# UWB-Adapter_Sch.net
KiCad netlist of a schematic drawn in Altium Designer
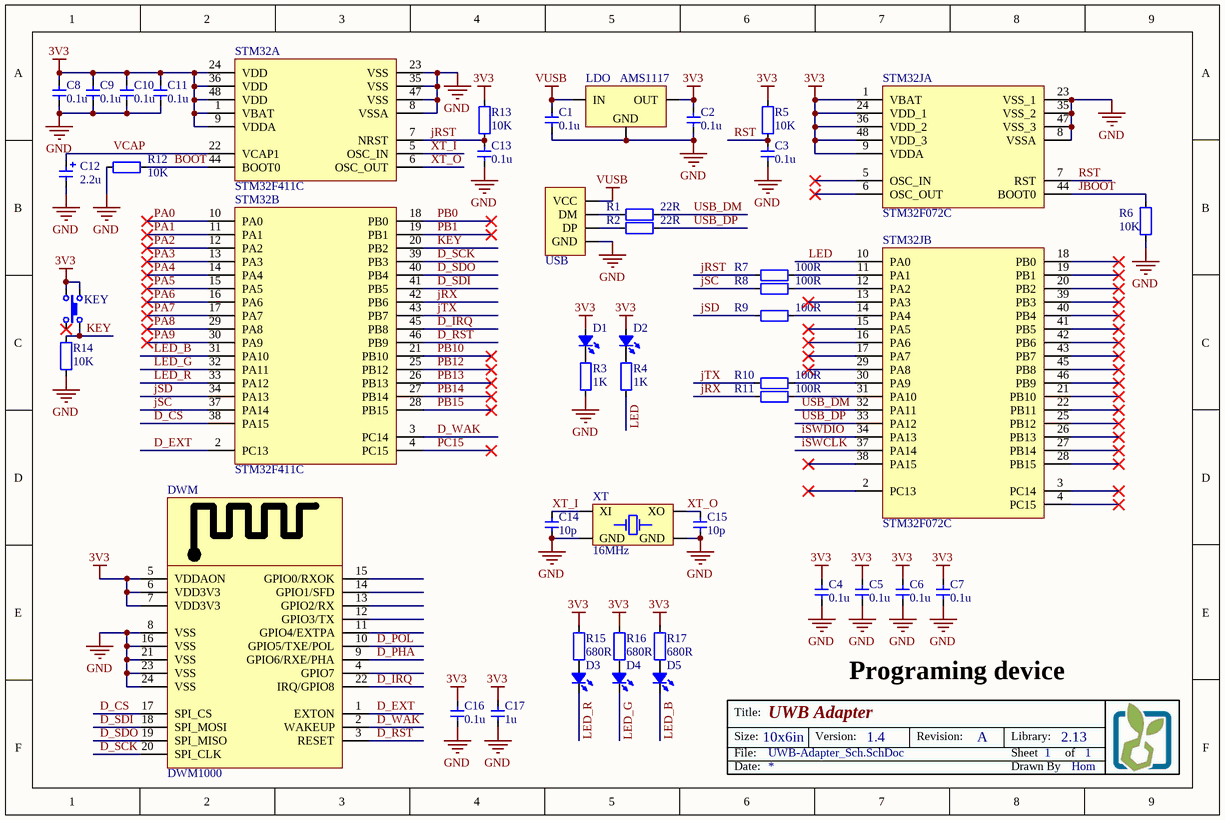
[diagram p0: UWB-Adapter_Sch.SchDoc]

(export (version "E")
  (design (tool "Eeschema 10.0.6"))
  (components
    (comp (ref "C1")
      (value "0.1u")
      (footprint "PCB_PassiveCap:CAP_0603")
      (description "Capacitor")
      (fields (field (name "Comment") "Cap_0603"))
      (libsource (lib "SCH_Passive") (part "Cap_0603"))
    )
    (comp (ref "C2")
      (value "0.1u")
      (footprint "PCB_PassiveCap:CAP_0603")
      (description "Capacitor")
      (fields (field (name "Comment") "Cap_0603"))
      (libsource (lib "SCH_Passive") (part "Cap_0603"))
    )
    (comp (ref "C3")
      (value "0.1u")
      (footprint "PCB_PassiveCap:CAP_0603")
      (description "Capacitor")
      (fields (field (name "Comment") "Cap_0603"))
      (libsource (lib "SCH_Passive") (part "Cap_0603"))
    )
    (comp (ref "C4")
      (value "0.1u")
      (footprint "PCB_PassiveCap:CAP_0603")
      (description "Capacitor")
      (fields (field (name "Comment") "Cap_0603"))
      (libsource (lib "SCH_Passive") (part "Cap_0603"))
    )
    (comp (ref "C5")
      (value "0.1u")
      (footprint "PCB_PassiveCap:CAP_0603")
      (description "Capacitor")
      (fields (field (name "Comment") "Cap_0603"))
      (libsource (lib "SCH_Passive") (part "Cap_0603"))
    )
    (comp (ref "C6")
      (value "0.1u")
      (footprint "PCB_PassiveCap:CAP_0603")
      (description "Capacitor")
      (fields (field (name "Comment") "Cap_0603"))
      (libsource (lib "SCH_Passive") (part "Cap_0603"))
    )
    (comp (ref "C7")
      (value "0.1u")
      (footprint "PCB_PassiveCap:CAP_0603")
      (description "Capacitor")
      (fields (field (name "Comment") "Cap_0603"))
      (libsource (lib "SCH_Passive") (part "Cap_0603"))
    )
    (comp (ref "C8")
      (value "0.1u")
      (footprint "PCB_PassiveCap:CAP_0603")
      (description "Capacitor")
      (fields (field (name "Comment") "Cap_0603"))
      (libsource (lib "SCH_Passive") (part "Cap_0603"))
    )
    (comp (ref "C9")
      (value "0.1u")
      (footprint "PCB_PassiveCap:CAP_0603")
      (description "Capacitor")
      (fields (field (name "Comment") "Cap_0603"))
      (libsource (lib "SCH_Passive") (part "Cap_0603"))
    )
    (comp (ref "C10")
      (value "0.1u")
      (footprint "PCB_PassiveCap:CAP_0603")
      (description "Capacitor")
      (fields (field (name "Comment") "Cap_0603"))
      (libsource (lib "SCH_Passive") (part "Cap_0603"))
    )
    (comp (ref "C11")
      (value "0.1u")
      (footprint "PCB_PassiveCap:CAP_0603")
      (description "Capacitor")
      (fields (field (name "Comment") "Cap_0603"))
      (libsource (lib "SCH_Passive") (part "Cap_0603"))
    )
    (comp (ref "C12")
      (value "2.2u")
      (footprint "PCB_PassiveCap:CAP_TAN_P0805")
      (description "Capacitor")
      (fields (field (name "Comment") "Cap_Tan_0805"))
      (libsource (lib "SCH_Passive") (part "Cap_Tan_0805"))
    )
    (comp (ref "C13")
      (value "0.1u")
      (footprint "PCB_PassiveCap:CAP_0603")
      (description "Capacitor")
      (fields (field (name "Comment") "Cap_0603"))
      (libsource (lib "SCH_Passive") (part "Cap_0603"))
    )
    (comp (ref "C14")
      (value "10p")
      (footprint "PCB_PassiveCap:CAP_0603")
      (description "Capacitor")
      (fields (field (name "Comment") "Cap_0603"))
      (libsource (lib "SCH_Passive") (part "Cap_0603"))
    )
    (comp (ref "C15")
      (value "10p")
      (footprint "PCB_PassiveCap:CAP_0603")
      (description "Capacitor")
      (fields (field (name "Comment") "Cap_0603"))
      (libsource (lib "SCH_Passive") (part "Cap_0603"))
    )
    (comp (ref "C16")
      (value "0.1u")
      (footprint "PCB_PassiveCap:CAP_0603")
      (description "Capacitor")
      (fields (field (name "Comment") "Cap_0603"))
      (libsource (lib "SCH_Passive") (part "Cap_0603"))
    )
    (comp (ref "C17")
      (value "1u")
      (footprint "PCB_PassiveCap:CAP_0603")
      (description "Capacitor")
      (fields (field (name "Comment") "Cap_0603"))
      (libsource (lib "SCH_Passive") (part "Cap_0603"))
    )
    (comp (ref "D1")
      (value "LED_0603")
      (footprint "PCB_ActiveLED:LED_0603_YELLOW")
      (description "LED")
      (libsource (lib "SCH_Active") (part "LED_0603"))
    )
    (comp (ref "D2")
      (value "LED_0603")
      (footprint "PCB_ActiveLED:LED_0603_ORANGE")
      (description "LED")
      (libsource (lib "SCH_Active") (part "LED_0603"))
    )
    (comp (ref "D3")
      (value "LED_0603")
      (footprint "PCB_ActiveLED:LED_0603_RED")
      (description "LED")
      (libsource (lib "SCH_Active") (part "LED_0603"))
    )
    (comp (ref "D4")
      (value "LED_0603")
      (footprint "PCB_ActiveLED:LED_0603_GREEN")
      (description "LED")
      (libsource (lib "SCH_Active") (part "LED_0603"))
    )
    (comp (ref "D5")
      (value "LED_0603")
      (footprint "PCB_ActiveLED:LED_0603_BLUE")
      (description "LED")
      (libsource (lib "SCH_Active") (part "LED_0603"))
    )
    (comp (ref "DWM")
      (value "DWM1000")
      (footprint "PCB_Module:DWM1000")
      (description "Module")
      (fields (field (name "MANUFACTURER") "Decawave Limited"))
      (libsource (lib "SCH_Module") (part "DWM1000"))
    )
    (comp (ref "KEY")
      (value "ButtonTACT")
      (footprint "PCB_Switch:ButtonTACT_3.5*3.55_90")
      (description "Button")
      (libsource (lib "SCH_Switch") (part "ButtonTACT"))
    )
    (comp (ref "LDO")
      (value "AMS1117")
      (footprint "PCB_IntegratedCircuit:SOT89-3")
      (description "Power")
      (libsource (lib "SCH_IntegratedCircuit") (part "LDO1117"))
    )
    (comp (ref "R1")
      (value "22R")
      (footprint "PCB_PassiveRes:RES_0603")
      (description "Resistor")
      (fields (field (name "Comment") "Res_0603"))
      (libsource (lib "") (part "Res_0603_1"))
    )
    (comp (ref "R2")
      (value "22R")
      (footprint "PCB_PassiveRes:RES_0603")
      (description "Resistor")
      (fields (field (name "Comment") "Res_0603"))
      (libsource (lib "") (part "Res_0603_1"))
    )
    (comp (ref "R3")
      (value "1K")
      (footprint "PCB_PassiveRes:RES_0603")
      (description "Resistor")
      (fields (field (name "Comment") "Res_0603"))
      (libsource (lib "SCH_Passive") (part "Res_0603"))
    )
    (comp (ref "R4")
      (value "1K")
      (footprint "PCB_PassiveRes:RES_0603")
      (description "Resistor")
      (fields (field (name "Comment") "Res_0603"))
      (libsource (lib "SCH_Passive") (part "Res_0603"))
    )
    (comp (ref "R5")
      (value "10K")
      (footprint "PCB_PassiveRes:RES_0603")
      (description "Resistor")
      (fields (field (name "Comment") "Res_0603"))
      (libsource (lib "SCH_Passive") (part "Res_0603"))
    )
    (comp (ref "R6")
      (value "10K")
      (footprint "PCB_PassiveRes:RES_0603")
      (description "Resistor")
      (fields (field (name "Comment") "Res_0603"))
      (libsource (lib "SCH_Passive") (part "Res_0603"))
    )
    (comp (ref "R7")
      (value "100R")
      (footprint "PCB_PassiveRes:RES_0603")
      (description "Resistor")
      (fields (field (name "Comment") "Res_0603"))
      (libsource (lib "") (part "Res_0603_1"))
    )
    (comp (ref "R8")
      (value "100R")
      (footprint "PCB_PassiveRes:RES_0603")
      (description "Resistor")
      (fields (field (name "Comment") "Res_0603"))
      (libsource (lib "") (part "Res_0603_1"))
    )
    (comp (ref "R9")
      (value "100R")
      (footprint "PCB_PassiveRes:RES_0603")
      (description "Resistor")
      (fields (field (name "Comment") "Res_0603"))
      (libsource (lib "") (part "Res_0603_1"))
    )
    (comp (ref "R10")
      (value "100R")
      (footprint "PCB_PassiveRes:RES_0603")
      (description "Resistor")
      (fields (field (name "Comment") "Res_0603"))
      (libsource (lib "") (part "Res_0603_1"))
    )
    (comp (ref "R11")
      (value "100R")
      (footprint "PCB_PassiveRes:RES_0603")
      (description "Resistor")
      (fields (field (name "Comment") "Res_0603"))
      (libsource (lib "") (part "Res_0603_1"))
    )
    (comp (ref "R12")
      (value "10K")
      (footprint "PCB_PassiveRes:RES_0603")
      (description "Resistor")
      (fields (field (name "Comment") "Res_0603"))
      (libsource (lib "") (part "Res_0603_2"))
    )
    (comp (ref "R13")
      (value "10K")
      (footprint "PCB_PassiveRes:RES_0603")
      (description "Resistor")
      (fields (field (name "Comment") "Res_0603"))
      (libsource (lib "SCH_Passive") (part "Res_0603"))
    )
    (comp (ref "R14")
      (value "10K")
      (footprint "PCB_PassiveRes:RES_0603")
      (description "Resistor")
      (fields (field (name "Comment") "Res_0603"))
      (libsource (lib "SCH_Passive") (part "Res_0603"))
    )
    (comp (ref "R15")
      (value "680R")
      (footprint "PCB_PassiveRes:RES_0603")
      (description "Resistor")
      (fields (field (name "Comment") "Res_0603"))
      (libsource (lib "SCH_Passive") (part "Res_0603"))
    )
    (comp (ref "R16")
      (value "680R")
      (footprint "PCB_PassiveRes:RES_0603")
      (description "Resistor")
      (fields (field (name "Comment") "Res_0603"))
      (libsource (lib "SCH_Passive") (part "Res_0603"))
    )
    (comp (ref "R17")
      (value "680R")
      (footprint "PCB_PassiveRes:RES_0603")
      (description "Resistor")
      (fields (field (name "Comment") "Res_0603"))
      (libsource (lib "SCH_Passive") (part "Res_0603"))
    )
    (comp (ref "STM32")
      (value "STM32F411C")
      (footprint "PCB_IntegratedCircuit:QFN_P0.5_48")
      (description "MCU")
      (libsource (lib "SCH_IntegratedCircuit") (part "STM32F4x1C"))
    )
    (comp (ref "STM32J")
      (value "STM32F072C")
      (footprint "PCB_IntegratedCircuit:LQFP_P0.5_48")
      (description "MCU")
      (libsource (lib "SCH_IntegratedCircuit") (part "STM32F103C"))
    )
    (comp (ref "USB")
      (value "USB_Plug_TypeA")
      (footprint "PCB_USB:USB_Plug_TypeA")
      (description "USB")
      (libsource (lib "SCH_USB") (part "USB_Plug_TypeA"))
    )
    (comp (ref "XT")
      (value "16MHz")
      (footprint "PCB_Oscillator:XT_2520_4")
      (description "Crystal Oscillator")
      (fields (field (name "Comment") "XTAL_2520_4P"))
      (libsource (lib "SCH_Oscillator") (part "XTAL_2520_4P"))
    )
  )
  (nets
    (net (code "1") (name "/BOOT") (class "Default")
      (node (ref "R12") (pin "1") (pinfunction "1_1") (pintype "passive"))
      (node (ref "STM32") (pin "44") (pinfunction "BOOT0_44") (pintype "passive"))
    )
    (net (code "2") (name "/D_CS") (class "Default")
      (node (ref "DWM") (pin "17") (pinfunction "SPI_CS_17") (pintype "passive"))
      (node (ref "STM32") (pin "38") (pinfunction "PA15_38") (pintype "passive"))
    )
    (net (code "3") (name "/D_EXT") (class "Default")
      (node (ref "DWM") (pin "1") (pinfunction "EXTON_1") (pintype "passive"))
      (node (ref "STM32") (pin "2") (pinfunction "PC13_2") (pintype "passive"))
    )
    (net (code "4") (name "/D_IRQ") (class "Default")
      (node (ref "DWM") (pin "22") (pinfunction "IRQ/GPIO8_22") (pintype "passive"))
      (node (ref "STM32") (pin "45") (pinfunction "PB8_45") (pintype "passive"))
    )
    (net (code "5") (name "/D_PHA") (class "Default")
      (node (ref "DWM") (pin "9") (pinfunction "GPIO6/RXE/PHA_9") (pintype "passive"))
    )
    (net (code "6") (name "/D_POL") (class "Default")
      (node (ref "DWM") (pin "10") (pinfunction "GPIO5/TXE/POL_10") (pintype "passive"))
    )
    (net (code "7") (name "/D_RST") (class "Default")
      (node (ref "DWM") (pin "3") (pinfunction "RESET_3") (pintype "passive"))
      (node (ref "STM32") (pin "46") (pinfunction "PB9_46") (pintype "passive"))
    )
    (net (code "8") (name "/D_SCK") (class "Default")
      (node (ref "DWM") (pin "20") (pinfunction "SPI_CLK_20") (pintype "passive"))
      (node (ref "STM32") (pin "39") (pinfunction "PB3_39") (pintype "passive"))
    )
    (net (code "9") (name "/D_SDI") (class "Default")
      (node (ref "DWM") (pin "18") (pinfunction "SPI_MOSI_18") (pintype "passive"))
      (node (ref "STM32") (pin "41") (pinfunction "PB5_41") (pintype "passive"))
    )
    (net (code "10") (name "/D_SDO") (class "Default")
      (node (ref "DWM") (pin "19") (pinfunction "SPI_MISO_19") (pintype "passive"))
      (node (ref "STM32") (pin "40") (pinfunction "PB4_40") (pintype "passive"))
    )
    (net (code "11") (name "/D_WAK") (class "Default")
      (node (ref "DWM") (pin "2") (pinfunction "WAKEUP_2") (pintype "passive"))
      (node (ref "STM32") (pin "3") (pinfunction "PC14_3") (pintype "passive"))
    )
    (net (code "12") (name "/JBOOT") (class "Default")
      (node (ref "R6") (pin "2") (pinfunction "2_2") (pintype "passive"))
      (node (ref "STM32J") (pin "44") (pinfunction "BOOT0_44") (pintype "passive"))
    )
    (net (code "13") (name "/KEY") (class "Default")
      (node (ref "KEY") (pin "2") (pinfunction "2_2") (pintype "passive"))
      (node (ref "R14") (pin "2") (pinfunction "2_2") (pintype "passive"))
      (node (ref "STM32") (pin "20") (pinfunction "PB2_20") (pintype "passive"))
    )
    (net (code "14") (name "/LED") (class "Default")
      (node (ref "R4") (pin "1") (pinfunction "1_1") (pintype "passive"))
      (node (ref "STM32J") (pin "10") (pinfunction "PA0_10") (pintype "passive"))
    )
    (net (code "15") (name "/LED_B") (class "Default")
      (node (ref "D5") (pin "2") (pinfunction "K_2") (pintype "passive"))
      (node (ref "STM32") (pin "31") (pinfunction "PA10_31") (pintype "passive"))
    )
    (net (code "16") (name "/LED_G") (class "Default")
      (node (ref "D4") (pin "2") (pinfunction "K_2") (pintype "passive"))
      (node (ref "STM32") (pin "32") (pinfunction "PA11_32") (pintype "passive"))
    )
    (net (code "17") (name "/LED_R") (class "Default")
      (node (ref "D3") (pin "2") (pinfunction "K_2") (pintype "passive"))
      (node (ref "STM32") (pin "33") (pinfunction "PA12_33") (pintype "passive"))
    )
    (net (code "18") (name "/PA0") (class "Default")
      (node (ref "STM32") (pin "10") (pinfunction "PA0_10") (pintype "passive+no_connect"))
    )
    (net (code "19") (name "/PA1") (class "Default")
      (node (ref "STM32") (pin "11") (pinfunction "PA1_11") (pintype "passive+no_connect"))
    )
    (net (code "20") (name "/PA2") (class "Default")
      (node (ref "STM32") (pin "12") (pinfunction "PA2_12") (pintype "passive+no_connect"))
    )
    (net (code "21") (name "/PA3") (class "Default")
      (node (ref "STM32") (pin "13") (pinfunction "PA3_13") (pintype "passive+no_connect"))
    )
    (net (code "22") (name "/PA4") (class "Default")
      (node (ref "STM32") (pin "14") (pinfunction "PA4_14") (pintype "passive+no_connect"))
    )
    (net (code "23") (name "/PA5") (class "Default")
      (node (ref "STM32") (pin "15") (pinfunction "PA5_15") (pintype "passive+no_connect"))
    )
    (net (code "24") (name "/PA6") (class "Default")
      (node (ref "STM32") (pin "16") (pinfunction "PA6_16") (pintype "passive+no_connect"))
    )
    (net (code "25") (name "/PA7") (class "Default")
      (node (ref "STM32") (pin "17") (pinfunction "PA7_17") (pintype "passive+no_connect"))
    )
    (net (code "26") (name "/PA8") (class "Default")
      (node (ref "STM32") (pin "29") (pinfunction "PA8_29") (pintype "passive+no_connect"))
    )
    (net (code "27") (name "/PA9") (class "Default")
      (node (ref "STM32") (pin "30") (pinfunction "PA9_30") (pintype "passive+no_connect"))
    )
    (net (code "28") (name "/PB0") (class "Default")
      (node (ref "STM32") (pin "18") (pinfunction "PB0_18") (pintype "passive+no_connect"))
    )
    (net (code "29") (name "/PB1") (class "Default")
      (node (ref "STM32") (pin "19") (pinfunction "PB1_19") (pintype "passive+no_connect"))
    )
    (net (code "30") (name "/PC15") (class "Default")
      (node (ref "STM32") (pin "4") (pinfunction "PC15_4") (pintype "passive+no_connect"))
    )
    (net (code "31") (name "/P~{B}10") (class "Default")
      (node (ref "STM32") (pin "21") (pinfunction "PB10_21") (pintype "passive+no_connect"))
    )
    (net (code "32") (name "/P~{B}12") (class "Default")
      (node (ref "STM32") (pin "25") (pinfunction "PB12_25") (pintype "passive+no_connect"))
    )
    (net (code "33") (name "/P~{B}13") (class "Default")
      (node (ref "STM32") (pin "26") (pinfunction "PB13_26") (pintype "passive+no_connect"))
    )
    (net (code "34") (name "/P~{B}14") (class "Default")
      (node (ref "STM32") (pin "27") (pinfunction "PB14_27") (pintype "passive+no_connect"))
    )
    (net (code "35") (name "/P~{B}15") (class "Default")
      (node (ref "STM32") (pin "28") (pinfunction "PB15_28") (pintype "passive+no_connect"))
    )
    (net (code "36") (name "/RST") (class "Default")
      (node (ref "C3") (pin "2") (pinfunction "2_2") (pintype "passive"))
      (node (ref "R5") (pin "1") (pinfunction "1_1") (pintype "passive"))
      (node (ref "STM32J") (pin "7") (pinfunction "RST_7") (pintype "passive"))
    )
    (net (code "37") (name "/USB_DM") (class "Default")
      (node (ref "R1") (pin "2") (pinfunction "2_2") (pintype "passive"))
      (node (ref "STM32J") (pin "32") (pinfunction "PA11_32") (pintype "passive"))
    )
    (net (code "38") (name "/USB_DP") (class "Default")
      (node (ref "R2") (pin "2") (pinfunction "2_2") (pintype "passive"))
      (node (ref "STM32J") (pin "33") (pinfunction "PA12_33") (pintype "passive"))
    )
    (net (code "39") (name "/VCAP") (class "Default")
      (node (ref "C12") (pin "1") (pinfunction "1_1") (pintype "passive"))
      (node (ref "STM32") (pin "22") (pinfunction "VCAP1_22") (pintype "passive"))
    )
    (net (code "40") (name "/XT_I") (class "Default")
      (node (ref "C14") (pin "2") (pinfunction "2_2") (pintype "passive"))
      (node (ref "STM32") (pin "5") (pinfunction "OSC_IN_5") (pintype "passive"))
      (node (ref "XT") (pin "1") (pinfunction "XI_1") (pintype "passive"))
    )
    (net (code "41") (name "/XT_O") (class "Default")
      (node (ref "C15") (pin "2") (pinfunction "2_2") (pintype "passive"))
      (node (ref "STM32") (pin "6") (pinfunction "OSC_OUT_6") (pintype "passive"))
      (node (ref "XT") (pin "3") (pinfunction "XO_3") (pintype "passive"))
    )
    (net (code "42") (name "/iSWCLK") (class "Default")
      (node (ref "STM32J") (pin "37") (pinfunction "PA14_37") (pintype "passive"))
    )
    (net (code "43") (name "/iSWDIO") (class "Default")
      (node (ref "STM32J") (pin "34") (pinfunction "PA13_34") (pintype "passive"))
    )
    (net (code "44") (name "/jRST") (class "Default")
      (node (ref "C13") (pin "2") (pinfunction "2_2") (pintype "passive"))
      (node (ref "R13") (pin "1") (pinfunction "1_1") (pintype "passive"))
      (node (ref "R7") (pin "1") (pinfunction "1_1") (pintype "passive"))
      (node (ref "STM32") (pin "7") (pinfunction "NRST_7") (pintype "passive"))
    )
    (net (code "45") (name "/jRX") (class "Default")
      (node (ref "R11") (pin "1") (pinfunction "1_1") (pintype "passive"))
      (node (ref "STM32") (pin "42") (pinfunction "PB6_42") (pintype "passive"))
    )
    (net (code "46") (name "/jSC") (class "Default")
      (node (ref "R8") (pin "1") (pinfunction "1_1") (pintype "passive"))
      (node (ref "STM32") (pin "37") (pinfunction "PA14_37") (pintype "passive"))
    )
    (net (code "47") (name "/jSD") (class "Default")
      (node (ref "R9") (pin "1") (pinfunction "1_1") (pintype "passive"))
      (node (ref "STM32") (pin "34") (pinfunction "PA13_34") (pintype "passive"))
    )
    (net (code "48") (name "/jTX") (class "Default")
      (node (ref "R10") (pin "1") (pinfunction "1_1") (pintype "passive"))
      (node (ref "STM32") (pin "43") (pinfunction "PB7_43") (pintype "passive"))
    )
    (net (code "49") (name "3V3") (class "Default")
      (node (ref "C10") (pin "2") (pinfunction "2_2") (pintype "passive"))
      (node (ref "C11") (pin "2") (pinfunction "2_2") (pintype "passive"))
      (node (ref "C16") (pin "1") (pinfunction "1_1") (pintype "passive"))
      (node (ref "C17") (pin "1") (pinfunction "1_1") (pintype "passive"))
      (node (ref "C2") (pin "2") (pinfunction "2_2") (pintype "passive"))
      (node (ref "C4") (pin "2") (pinfunction "2_2") (pintype "passive"))
      (node (ref "C5") (pin "2") (pinfunction "2_2") (pintype "passive"))
      (node (ref "C6") (pin "2") (pinfunction "2_2") (pintype "passive"))
      (node (ref "C7") (pin "2") (pinfunction "2_2") (pintype "passive"))
      (node (ref "C8") (pin "2") (pinfunction "2_2") (pintype "passive"))
      (node (ref "C9") (pin "2") (pinfunction "2_2") (pintype "passive"))
      (node (ref "D1") (pin "1") (pinfunction "A_1") (pintype "passive"))
      (node (ref "D2") (pin "1") (pinfunction "A_1") (pintype "passive"))
      (node (ref "DWM") (pin "5") (pinfunction "VDDAON_5") (pintype "passive"))
      (node (ref "DWM") (pin "6") (pinfunction "VDD3V3_6") (pintype "passive"))
      (node (ref "DWM") (pin "7") (pinfunction "VDD3V3_7") (pintype "passive"))
      (node (ref "KEY") (pin "1") (pinfunction "1_1") (pintype "passive"))
      (node (ref "KEY") (pin "3") (pinfunction "3_3") (pintype "passive"))
      (node (ref "LDO") (pin "2") (pinfunction "OUT_2") (pintype "power_in"))
      (node (ref "R13") (pin "2") (pinfunction "2_2") (pintype "passive"))
      (node (ref "R15") (pin "2") (pinfunction "2_2") (pintype "passive"))
      (node (ref "R16") (pin "2") (pinfunction "2_2") (pintype "passive"))
      (node (ref "R17") (pin "2") (pinfunction "2_2") (pintype "passive"))
      (node (ref "R5") (pin "2") (pinfunction "2_2") (pintype "passive"))
      (node (ref "STM32") (pin "1") (pinfunction "VBAT_1") (pintype "passive"))
      (node (ref "STM32") (pin "24") (pinfunction "VDD_24") (pintype "passive"))
      (node (ref "STM32") (pin "36") (pinfunction "VDD_36") (pintype "passive"))
      (node (ref "STM32") (pin "48") (pinfunction "VDD_48") (pintype "passive"))
      (node (ref "STM32") (pin "9") (pinfunction "VDDA_9") (pintype "passive"))
      (node (ref "STM32J") (pin "1") (pinfunction "VBAT_1") (pintype "passive"))
      (node (ref "STM32J") (pin "24") (pinfunction "VDD_1_24") (pintype "passive"))
      (node (ref "STM32J") (pin "36") (pinfunction "VDD_2_36") (pintype "passive"))
      (node (ref "STM32J") (pin "48") (pinfunction "VDD_3_48") (pintype "passive"))
      (node (ref "STM32J") (pin "9") (pinfunction "VDDA_9") (pintype "passive"))
    )
    (net (code "50") (name "GND") (class "Default")
      (node (ref "C1") (pin "1") (pinfunction "1_1") (pintype "passive"))
      (node (ref "C10") (pin "1") (pinfunction "1_1") (pintype "passive"))
      (node (ref "C11") (pin "1") (pinfunction "1_1") (pintype "passive"))
      (node (ref "C12") (pin "2") (pinfunction "2_2") (pintype "passive"))
      (node (ref "C13") (pin "1") (pinfunction "1_1") (pintype "passive"))
      (node (ref "C14") (pin "1") (pinfunction "1_1") (pintype "passive"))
      (node (ref "C15") (pin "1") (pinfunction "1_1") (pintype "passive"))
      (node (ref "C16") (pin "2") (pinfunction "2_2") (pintype "passive"))
      (node (ref "C17") (pin "2") (pinfunction "2_2") (pintype "passive"))
      (node (ref "C2") (pin "1") (pinfunction "1_1") (pintype "passive"))
      (node (ref "C3") (pin "1") (pinfunction "1_1") (pintype "passive"))
      (node (ref "C4") (pin "1") (pinfunction "1_1") (pintype "passive"))
      (node (ref "C5") (pin "1") (pinfunction "1_1") (pintype "passive"))
      (node (ref "C6") (pin "1") (pinfunction "1_1") (pintype "passive"))
      (node (ref "C7") (pin "1") (pinfunction "1_1") (pintype "passive"))
      (node (ref "C8") (pin "1") (pinfunction "1_1") (pintype "passive"))
      (node (ref "C9") (pin "1") (pinfunction "1_1") (pintype "passive"))
      (node (ref "DWM") (pin "16") (pinfunction "VSS_16") (pintype "passive"))
      (node (ref "DWM") (pin "21") (pinfunction "VSS_21") (pintype "passive"))
      (node (ref "DWM") (pin "23") (pinfunction "VSS_23") (pintype "passive"))
      (node (ref "DWM") (pin "24") (pinfunction "VSS_24") (pintype "passive"))
      (node (ref "DWM") (pin "8") (pinfunction "VSS_8") (pintype "passive"))
      (node (ref "LDO") (pin "1") (pinfunction "GND_1") (pintype "power_in"))
      (node (ref "R12") (pin "2") (pinfunction "2_2") (pintype "passive"))
      (node (ref "R14") (pin "1") (pinfunction "1_1") (pintype "passive"))
      (node (ref "R3") (pin "1") (pinfunction "1_1") (pintype "passive"))
      (node (ref "R6") (pin "1") (pinfunction "1_1") (pintype "passive"))
      (node (ref "STM32") (pin "23") (pinfunction "VSS_23") (pintype "passive"))
      (node (ref "STM32") (pin "35") (pinfunction "VSS_35") (pintype "passive"))
      (node (ref "STM32") (pin "47") (pinfunction "VSS_47") (pintype "passive"))
      (node (ref "STM32") (pin "8") (pinfunction "VSSA_8") (pintype "passive"))
      (node (ref "STM32J") (pin "23") (pinfunction "VSS_1_23") (pintype "passive"))
      (node (ref "STM32J") (pin "35") (pinfunction "VSS_2_35") (pintype "passive"))
      (node (ref "STM32J") (pin "47") (pinfunction "VSS_3_47") (pintype "passive"))
      (node (ref "STM32J") (pin "8") (pinfunction "VSSA_8") (pintype "passive"))
      (node (ref "USB") (pin "4") (pinfunction "GND_4") (pintype "passive"))
      (node (ref "XT") (pin "2") (pinfunction "GND_2") (pintype "passive"))
      (node (ref "XT") (pin "4") (pinfunction "GND_4") (pintype "passive"))
    )
    (net (code "51") (name "Net-(D1-K)") (class "Default")
      (node (ref "D1") (pin "2") (pinfunction "K_2") (pintype "passive"))
      (node (ref "R3") (pin "2") (pinfunction "2_2") (pintype "passive"))
    )
    (net (code "52") (name "Net-(D2-K)") (class "Default")
      (node (ref "D2") (pin "2") (pinfunction "K_2") (pintype "passive"))
      (node (ref "R4") (pin "2") (pinfunction "2_2") (pintype "passive"))
    )
    (net (code "53") (name "Net-(D3-A)") (class "Default")
      (node (ref "D3") (pin "1") (pinfunction "A_1") (pintype "passive"))
      (node (ref "R15") (pin "1") (pinfunction "1_1") (pintype "passive"))
    )
    (net (code "54") (name "Net-(D4-A)") (class "Default")
      (node (ref "D4") (pin "1") (pinfunction "A_1") (pintype "passive"))
      (node (ref "R16") (pin "1") (pinfunction "1_1") (pintype "passive"))
    )
    (net (code "55") (name "Net-(D5-A)") (class "Default")
      (node (ref "D5") (pin "1") (pinfunction "A_1") (pintype "passive"))
      (node (ref "R17") (pin "1") (pinfunction "1_1") (pintype "passive"))
    )
    (net (code "56") (name "Net-(STM32JB-PA1)") (class "Default")
      (node (ref "R7") (pin "2") (pinfunction "2_2") (pintype "passive"))
      (node (ref "STM32J") (pin "11") (pinfunction "PA1_11") (pintype "passive"))
    )
    (net (code "57") (name "Net-(STM32JB-PA2)") (class "Default")
      (node (ref "R8") (pin "2") (pinfunction "2_2") (pintype "passive"))
      (node (ref "STM32J") (pin "12") (pinfunction "PA2_12") (pintype "passive"))
    )
    (net (code "58") (name "Net-(STM32JB-PA4)") (class "Default")
      (node (ref "R9") (pin "2") (pinfunction "2_2") (pintype "passive"))
      (node (ref "STM32J") (pin "14") (pinfunction "PA4_14") (pintype "passive"))
    )
    (net (code "59") (name "Net-(STM32JB-PA9)") (class "Default")
      (node (ref "R10") (pin "2") (pinfunction "2_2") (pintype "passive"))
      (node (ref "STM32J") (pin "30") (pinfunction "PA9_30") (pintype "passive"))
    )
    (net (code "60") (name "Net-(STM32JB-PA10)") (class "Default")
      (node (ref "R11") (pin "2") (pinfunction "2_2") (pintype "passive"))
      (node (ref "STM32J") (pin "31") (pinfunction "PA10_31") (pintype "passive"))
    )
    (net (code "61") (name "Net-(USB-DM)") (class "Default")
      (node (ref "R1") (pin "1") (pinfunction "1_1") (pintype "passive"))
      (node (ref "USB") (pin "2") (pinfunction "DM_2") (pintype "passive"))
    )
    (net (code "62") (name "Net-(USB-DP)") (class "Default")
      (node (ref "R2") (pin "1") (pinfunction "1_1") (pintype "passive"))
      (node (ref "USB") (pin "3") (pinfunction "DP_3") (pintype "passive"))
    )
    (net (code "63") (name "VUSB") (class "Default")
      (node (ref "C1") (pin "2") (pinfunction "2_2") (pintype "passive"))
      (node (ref "LDO") (pin "3") (pinfunction "IN_3") (pintype "power_in"))
      (node (ref "USB") (pin "1") (pinfunction "VCC_1") (pintype "passive"))
    )
    (net (code "64") (name "unconnected-(DWM-GPIO0{slash}RXOK-Pad15)") (class "Default")
      (node (ref "DWM") (pin "15") (pinfunction "GPIO0/RXOK_15") (pintype "passive"))
    )
    (net (code "65") (name "unconnected-(DWM-GPIO1{slash}SFD-Pad14)") (class "Default")
      (node (ref "DWM") (pin "14") (pinfunction "GPIO1/SFD_14") (pintype "passive"))
    )
    (net (code "66") (name "unconnected-(DWM-GPIO2{slash}RX-Pad13)") (class "Default")
      (node (ref "DWM") (pin "13") (pinfunction "GPIO2/RX_13") (pintype "passive"))
    )
    (net (code "67") (name "unconnected-(DWM-GPIO3{slash}TX-Pad12)") (class "Default")
      (node (ref "DWM") (pin "12") (pinfunction "GPIO3/TX_12") (pintype "passive"))
    )
    (net (code "68") (name "unconnected-(DWM-GPIO4{slash}EXTPA-Pad11)") (class "Default")
      (node (ref "DWM") (pin "11") (pinfunction "GPIO4/EXTPA_11") (pintype "passive"))
    )
    (net (code "69") (name "unconnected-(DWM-GPIO7-Pad4)") (class "Default")
      (node (ref "DWM") (pin "4") (pinfunction "GPIO7_4") (pintype "passive"))
    )
    (net (code "70") (name "unconnected-(KEY-Pad4)") (class "Default")
      (node (ref "KEY") (pin "4") (pinfunction "4_4") (pintype "passive+no_connect"))
    )
    (net (code "71") (name "unconnected-(STM32JA-OSC_IN-Pad5)") (class "Default")
      (node (ref "STM32J") (pin "5") (pinfunction "OSC_IN_5") (pintype "passive+no_connect"))
    )
    (net (code "72") (name "unconnected-(STM32JA-OSC_OUT-Pad6)") (class "Default")
      (node (ref "STM32J") (pin "6") (pinfunction "OSC_OUT_6") (pintype "passive+no_connect"))
    )
    (net (code "73") (name "unconnected-(STM32JB-PA3-Pad13)") (class "Default")
      (node (ref "STM32J") (pin "13") (pinfunction "PA3_13") (pintype "passive+no_connect"))
    )
    (net (code "74") (name "unconnected-(STM32JB-PA5-Pad15)") (class "Default")
      (node (ref "STM32J") (pin "15") (pinfunction "PA5_15") (pintype "passive+no_connect"))
    )
    (net (code "75") (name "unconnected-(STM32JB-PA6-Pad16)") (class "Default")
      (node (ref "STM32J") (pin "16") (pinfunction "PA6_16") (pintype "passive+no_connect"))
    )
    (net (code "76") (name "unconnected-(STM32JB-PA7-Pad17)") (class "Default")
      (node (ref "STM32J") (pin "17") (pinfunction "PA7_17") (pintype "passive+no_connect"))
    )
    (net (code "77") (name "unconnected-(STM32JB-PA8-Pad29)") (class "Default")
      (node (ref "STM32J") (pin "29") (pinfunction "PA8_29") (pintype "passive+no_connect"))
    )
    (net (code "78") (name "unconnected-(STM32JB-PA15-Pad38)") (class "Default")
      (node (ref "STM32J") (pin "38") (pinfunction "PA15_38") (pintype "passive+no_connect"))
    )
    (net (code "79") (name "unconnected-(STM32JB-PB0-Pad18)") (class "Default")
      (node (ref "STM32J") (pin "18") (pinfunction "PB0_18") (pintype "passive+no_connect"))
    )
    (net (code "80") (name "unconnected-(STM32JB-PB1-Pad19)") (class "Default")
      (node (ref "STM32J") (pin "19") (pinfunction "PB1_19") (pintype "passive+no_connect"))
    )
    (net (code "81") (name "unconnected-(STM32JB-PB2-Pad20)") (class "Default")
      (node (ref "STM32J") (pin "20") (pinfunction "PB2_20") (pintype "passive+no_connect"))
    )
    (net (code "82") (name "unconnected-(STM32JB-PB3-Pad39)") (class "Default")
      (node (ref "STM32J") (pin "39") (pinfunction "PB3_39") (pintype "passive+no_connect"))
    )
    (net (code "83") (name "unconnected-(STM32JB-PB4-Pad40)") (class "Default")
      (node (ref "STM32J") (pin "40") (pinfunction "PB4_40") (pintype "passive+no_connect"))
    )
    (net (code "84") (name "unconnected-(STM32JB-PB5-Pad41)") (class "Default")
      (node (ref "STM32J") (pin "41") (pinfunction "PB5_41") (pintype "passive+no_connect"))
    )
    (net (code "85") (name "unconnected-(STM32JB-PB6-Pad42)") (class "Default")
      (node (ref "STM32J") (pin "42") (pinfunction "PB6_42") (pintype "passive+no_connect"))
    )
    (net (code "86") (name "unconnected-(STM32JB-PB7-Pad43)") (class "Default")
      (node (ref "STM32J") (pin "43") (pinfunction "PB7_43") (pintype "passive+no_connect"))
    )
    (net (code "87") (name "unconnected-(STM32JB-PB8-Pad45)") (class "Default")
      (node (ref "STM32J") (pin "45") (pinfunction "PB8_45") (pintype "passive+no_connect"))
    )
    (net (code "88") (name "unconnected-(STM32JB-PB9-Pad46)") (class "Default")
      (node (ref "STM32J") (pin "46") (pinfunction "PB9_46") (pintype "passive+no_connect"))
    )
    (net (code "89") (name "unconnected-(STM32JB-PB10-Pad21)") (class "Default")
      (node (ref "STM32J") (pin "21") (pinfunction "PB10_21") (pintype "passive+no_connect"))
    )
    (net (code "90") (name "unconnected-(STM32JB-PB11-Pad22)") (class "Default")
      (node (ref "STM32J") (pin "22") (pinfunction "PB11_22") (pintype "passive+no_connect"))
    )
    (net (code "91") (name "unconnected-(STM32JB-PB12-Pad25)") (class "Default")
      (node (ref "STM32J") (pin "25") (pinfunction "PB12_25") (pintype "passive+no_connect"))
    )
    (net (code "92") (name "unconnected-(STM32JB-PB13-Pad26)") (class "Default")
      (node (ref "STM32J") (pin "26") (pinfunction "PB13_26") (pintype "passive+no_connect"))
    )
    (net (code "93") (name "unconnected-(STM32JB-PB14-Pad27)") (class "Default")
      (node (ref "STM32J") (pin "27") (pinfunction "PB14_27") (pintype "passive+no_connect"))
    )
    (net (code "94") (name "unconnected-(STM32JB-PB15-Pad28)") (class "Default")
      (node (ref "STM32J") (pin "28") (pinfunction "PB15_28") (pintype "passive+no_connect"))
    )
    (net (code "95") (name "unconnected-(STM32JB-PC13-Pad2)") (class "Default")
      (node (ref "STM32J") (pin "2") (pinfunction "PC13_2") (pintype "passive+no_connect"))
    )
    (net (code "96") (name "unconnected-(STM32JB-PC14-Pad3)") (class "Default")
      (node (ref "STM32J") (pin "3") (pinfunction "PC14_3") (pintype "passive+no_connect"))
    )
    (net (code "97") (name "unconnected-(STM32JB-PC15-Pad4)") (class "Default")
      (node (ref "STM32J") (pin "4") (pinfunction "PC15_4") (pintype "passive+no_connect"))
    )
  )
)
